# Sheet2.net
KiCad netlist of a schematic drawn in Altium Designer
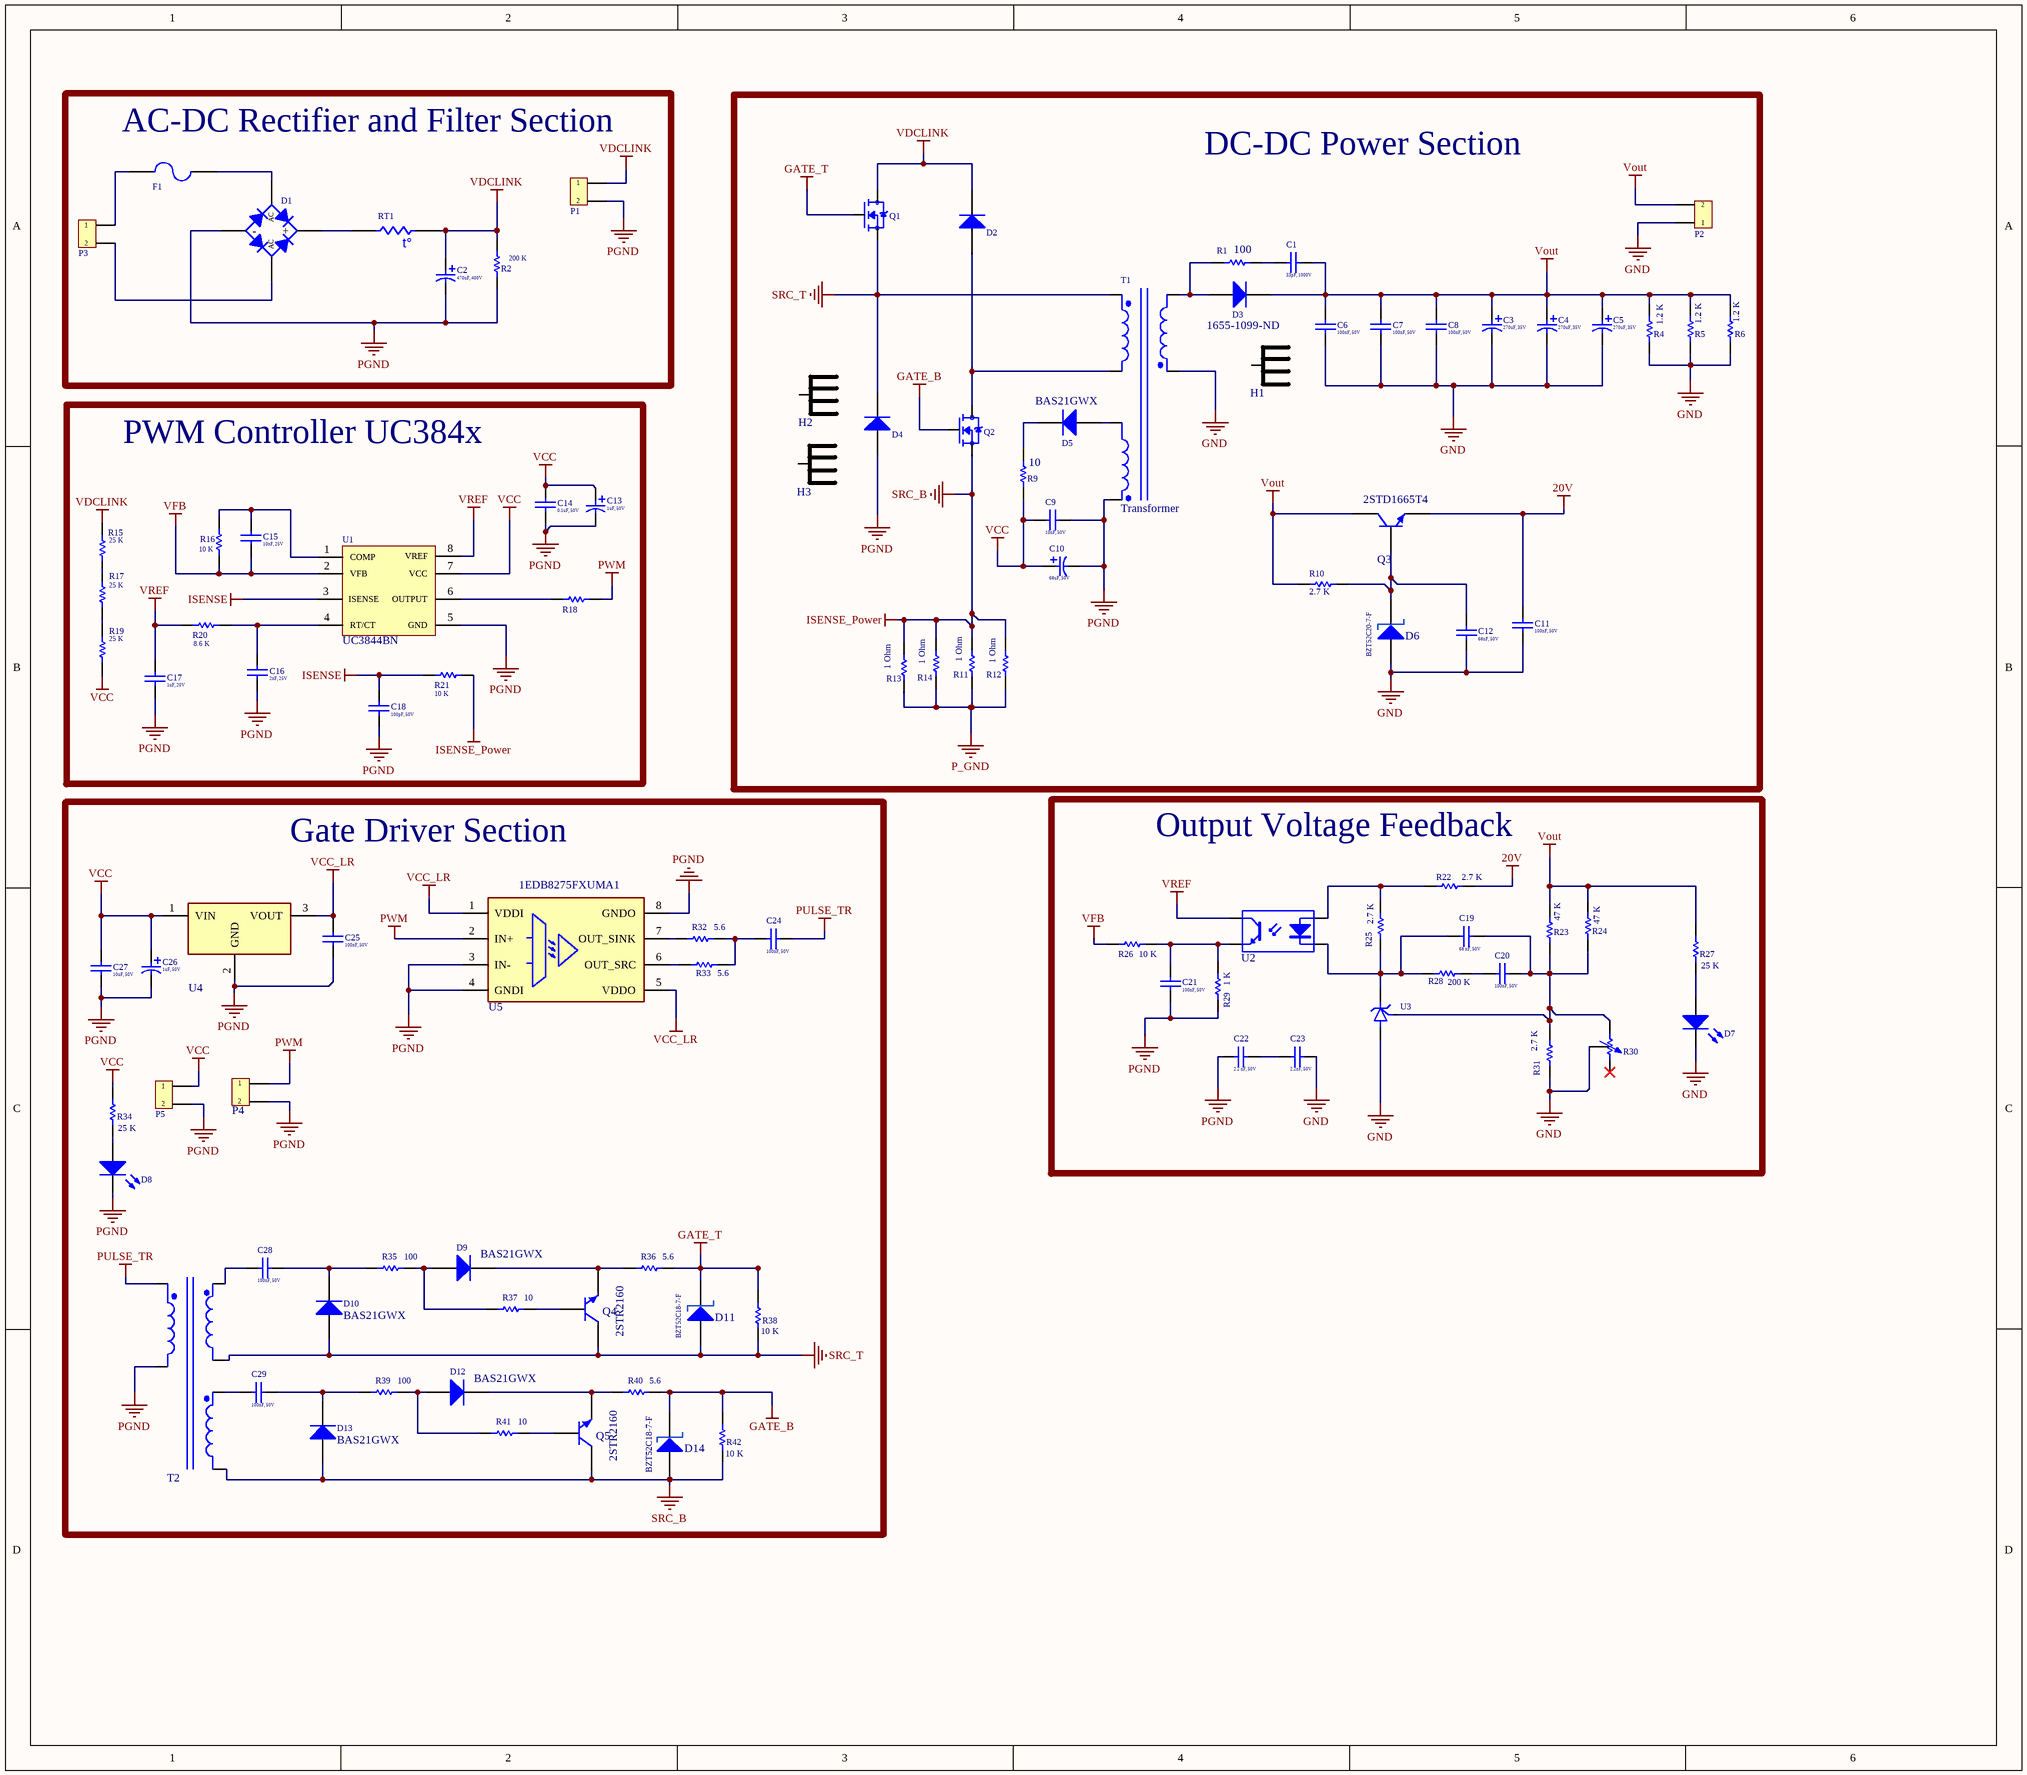
[diagram p0: Sheet2.SchDoc]

(export (version "E")
  (design (tool "Eeschema 10.0.6"))
  (components
    (comp (ref "C1")
      (value "33pF, 1000V")
      (footprint "Capacitor Polyester High Voltage DIP")
      (description "Ceramic & Polyester Capacitor")
      (fields (field (name "Comment") "(DIGIKEY Part Number)"))
      (libsource (lib "M_Derogarian Altium Library") (part "Capacitors Non-Electrolytic"))
    )
    (comp (ref "C2")
      (value "470uF, 400V")
      (footprint "Capacitor Aluminum Electrolytic DIP 20*36.5*10")
      (description "Aluminum Electrolytic Capacitors")
      (fields (field (name "MF") "Nichicon") (field (name "MP") "UVR2A471MHD"))
      (libsource (lib "M_Derogarian Altium Library") (part "Capacitors Electrolytic"))
    )
    (comp (ref "C3")
      (value "270uF, 35V")
      (footprint "Capacitor Aluminum Electrolytic DIP 10*13*5")
      (description "Aluminum Electrolytic Capacitors")
      (fields (field (name "MF") "Nichicon") (field (name "MP") "UVR2A471MHD"))
      (libsource (lib "M_Derogarian Altium Library") (part "Capacitors Electrolytic"))
    )
    (comp (ref "C4")
      (value "270uF, 35V")
      (footprint "Capacitor Aluminum Electrolytic DIP 10*13*5")
      (description "Aluminum Electrolytic Capacitors")
      (fields (field (name "MF") "Nichicon") (field (name "MP") "UVR2A471MHD"))
      (libsource (lib "M_Derogarian Altium Library") (part "Capacitors Electrolytic"))
    )
    (comp (ref "C5")
      (value "270uF, 35V")
      (footprint "Capacitor Aluminum Electrolytic DIP 10*13*5")
      (description "Aluminum Electrolytic Capacitors")
      (fields (field (name "MF") "Nichicon") (field (name "MP") "UVR2A471MHD"))
      (libsource (lib "M_Derogarian Altium Library") (part "Capacitors Electrolytic"))
    )
    (comp (ref "C6")
      (value "100nF, 50V")
      (footprint "Capacitor Ceramic SMD 1206")
      (description "Ceramic & Polyester Capacitor")
      (fields (field (name "Comment") "478-KGM21NR71H104JTTR-ND"))
      (libsource (lib "M_Derogarian Altium Library") (part "Capacitors Non-Electrolytic"))
    )
    (comp (ref "C7")
      (value "100nF, 50V")
      (footprint "Capacitor Ceramic SMD 1206")
      (description "Ceramic & Polyester Capacitor")
      (fields (field (name "Comment") "478-KGM21NR71H104JTTR-ND"))
      (libsource (lib "M_Derogarian Altium Library") (part "Capacitors Non-Electrolytic"))
    )
    (comp (ref "C8")
      (value "100nF, 50V")
      (footprint "Capacitor Ceramic SMD 1206")
      (description "Ceramic & Polyester Capacitor")
      (fields (field (name "Comment") "478-KGM21NR71H104JTTR-ND"))
      (libsource (lib "M_Derogarian Altium Library") (part "Capacitors Non-Electrolytic"))
    )
    (comp (ref "C9")
      (value "10nF, 50V")
      (footprint "Capacitor Ceramic SMD 805")
      (description "Ceramic & Polyester Capacitor")
      (fields (field (name "Comment") "GRM2195C1H103JA01D"))
      (libsource (lib "M_Derogarian Altium Library") (part "Capacitors Non-Electrolytic"))
    )
    (comp (ref "C10")
      (value "68uF, 50V")
      (footprint "Capacitor Aluminum Electrolytic DIP 5*7.5*2.5")
      (description "Aluminum Electrolytic Capacitors")
      (fields (field (name "MF") "Nichicon") (field (name "MP") "UVR2A471MHD"))
      (libsource (lib "M_Derogarian Altium Library") (part "Capacitors Electrolytic"))
    )
    (comp (ref "C11")
      (value "100nF, 50V")
      (footprint "Capacitor Ceramic SMD 1206")
      (description "Ceramic & Polyester Capacitor")
      (fields (field (name "Comment") "478-KGM21NR71H104JTTR-ND"))
      (libsource (lib "M_Derogarian Altium Library") (part "Capacitors Non-Electrolytic"))
    )
    (comp (ref "C12")
      (value "68nF, 50V")
      (footprint "Capacitor Ceramic SMD 1206")
      (description "Ceramic & Polyester Capacitor")
      (fields (field (name "Comment") "KGM21NR71H683JT"))
      (libsource (lib "M_Derogarian Altium Library") (part "Capacitors Non-Electrolytic"))
    )
    (comp (ref "C13")
      (value "1uF, 50V")
      (footprint "Capacitor Aluminum Electrolytic DIP 5*7.5*2.5")
      (description "Aluminum Electrolytic Capacitors")
      (fields (field (name "MF") "Nichicon") (field (name "MP") "UVR2A471MHD"))
      (libsource (lib "M_Derogarian Altium Library") (part "Capacitors Electrolytic"))
    )
    (comp (ref "C14")
      (value "0.1uF, 50V")
      (footprint "Capacitor Ceramic SMD 805")
      (description "Ceramic & Polyester Capacitor")
      (fields (field (name "Comment") "399-C0805C104J5RAC7800TR-ND"))
      (libsource (lib "M_Derogarian Altium Library") (part "Capacitors Non-Electrolytic"))
    )
    (comp (ref "C15")
      (value "10nF, 25V")
      (footprint "Capacitor Ceramic SMD 805")
      (description "Ceramic & Polyester Capacitor")
      (fields (field (name "Comment") "490-1642-2-ND"))
      (libsource (lib "M_Derogarian Altium Library") (part "Capacitors Non-Electrolytic"))
    )
    (comp (ref "C16")
      (value "2nF, 25V")
      (footprint "Capacitor Ceramic SMD 805")
      (description "Ceramic & Polyester Capacitor")
      (fields (field (name "Comment") "490-1627-2-ND"))
      (libsource (lib "M_Derogarian Altium Library") (part "Capacitors Non-Electrolytic"))
    )
    (comp (ref "C17")
      (value "1uF, 20V")
      (footprint "Capacitor Ceramic SMD 805")
      (description "Ceramic & Polyester Capacitor")
      (fields (field (name "Comment") "311-3498-2-ND"))
      (libsource (lib "M_Derogarian Altium Library") (part "Capacitors Non-Electrolytic"))
    )
    (comp (ref "C18")
      (value "100pF, 50V")
      (footprint "Capacitor Ceramic SMD 805")
      (description "Ceramic & Polyester Capacitor")
      (fields (field (name "Comment") "399-C0805C101J5GAC7800TR-ND"))
      (libsource (lib "M_Derogarian Altium Library") (part "Capacitors Non-Electrolytic"))
    )
    (comp (ref "C19")
      (value "68 nF, 50V")
      (footprint "Capacitor Ceramic SMD 805")
      (description "Ceramic & Polyester Capacitor")
      (fields (field (name "Comment") "KGM21NR71H683JT"))
      (libsource (lib "M_Derogarian Altium Library") (part "Capacitors Non-Electrolytic"))
    )
    (comp (ref "C20")
      (value "100nF, 50V")
      (footprint "Capacitor Ceramic SMD 805")
      (description "Ceramic & Polyester Capacitor")
      (fields (field (name "Comment") "C0805C104J5RAC7800"))
      (libsource (lib "M_Derogarian Altium Library") (part "Capacitors Non-Electrolytic"))
    )
    (comp (ref "C21")
      (value "100nF, 50V")
      (footprint "Capacitor Ceramic SMD 805")
      (description "Ceramic & Polyester Capacitor")
      (fields (field (name "Comment") "C0805C104J5RAC7800"))
      (libsource (lib "M_Derogarian Altium Library") (part "Capacitors Non-Electrolytic"))
    )
    (comp (ref "C22")
      (value "2.2 nF, 50V")
      (footprint "Capacitor Polyester High Voltage DIP")
      (description "Ceramic & Polyester Capacitor")
      (fields (field (name "Comment") "(DIGIKEY Part Number)"))
      (libsource (lib "M_Derogarian Altium Library") (part "Capacitors Non-Electrolytic"))
    )
    (comp (ref "C23")
      (value "2.2nF, 50V")
      (footprint "Capacitor Polyester High Voltage DIP")
      (description "Ceramic & Polyester Capacitor")
      (fields (field (name "Comment") "(DIGIKEY Part Number)"))
      (libsource (lib "M_Derogarian Altium Library") (part "Capacitors Non-Electrolytic"))
    )
    (comp (ref "C24")
      (value "100nF, 50V")
      (footprint "Capacitor Ceramic SMD 805")
      (description "Ceramic & Polyester Capacitor")
      (fields (field (name "Comment") "C0805C104J5RAC7800"))
      (libsource (lib "M_Derogarian Altium Library") (part "Capacitors Non-Electrolytic"))
    )
    (comp (ref "C25")
      (value "100nF, 50V")
      (footprint "Capacitor Ceramic SMD 805")
      (description "Ceramic & Polyester Capacitor")
      (fields (field (name "Comment") "C0805C104J5RAC7800"))
      (libsource (lib "M_Derogarian Altium Library") (part "Capacitors Non-Electrolytic"))
    )
    (comp (ref "C26")
      (value "1uF, 50V")
      (footprint "Capacitor Aluminum Electrolytic DIP 5*7.5*2.5")
      (description "Aluminum Electrolytic Capacitors")
      (fields (field (name "MF") "Nichicon") (field (name "MP") "UVR2A471MHD"))
      (libsource (lib "M_Derogarian Altium Library") (part "Capacitors Electrolytic"))
    )
    (comp (ref "C27")
      (value "10uF, 50V")
      (footprint "Capacitor Ceramic SMD 805")
      (description "Ceramic & Polyester Capacitor")
      (fields (field (name "Comment") "490-18663-2-ND"))
      (libsource (lib "M_Derogarian Altium Library") (part "Capacitors Non-Electrolytic"))
    )
    (comp (ref "C28")
      (value "100nF, 50V")
      (footprint "Capacitor Ceramic SMD 805")
      (description "Ceramic & Polyester Capacitor")
      (fields (field (name "Comment") "C0805C104J5RAC7800"))
      (libsource (lib "M_Derogarian Altium Library") (part "Capacitors Non-Electrolytic"))
    )
    (comp (ref "C29")
      (value "100nF, 50V")
      (footprint "Capacitor Ceramic SMD 805")
      (description "Ceramic & Polyester Capacitor")
      (fields (field (name "Comment") "C0805C104J5RAC7800"))
      (libsource (lib "M_Derogarian Altium Library") (part "Capacitors Non-Electrolytic"))
    )
    (comp (ref "D1")
      (value "31-GBU10V08-TU-ND")
      (footprint "Bridge Rectifier 1Phase 600V 10A GBJ")
      (description "Bridge Rectifier Single Phase Standard")
      (fields (field (name "PUBLISHER") "Altium Limited"))
      (libsource (lib "M_Derogarian Altium Library") (part "Single Phase Bridge Rectifier"))
    )
    (comp (ref "D2")
      (value "31-S5KP5M-13TR-ND")
      (footprint "Diode SMD POWERDI5")
      (description "Through Hole & SMD Diode")
      (fields (field (name "PUBLISHER") "Altium Limited"))
      (libsource (lib "M_Derogarian Altium Library") (part "Diode"))
    )
    (comp (ref "D3")
      (value "1655-1099-ND")
      (footprint "Diode DIP ITO-220AC")
      (description "Through Hole & SMD Diode")
      (fields (field (name "PUBLISHER") "Altium Limited"))
      (libsource (lib "M_Derogarian Altium Library") (part "Diode"))
    )
    (comp (ref "D4")
      (value "31-S5KP5M-13TR-ND")
      (footprint "Diode SMD POWERDI5")
      (description "Through Hole & SMD Diode")
      (fields (field (name "PUBLISHER") "Altium Limited"))
      (libsource (lib "M_Derogarian Altium Library") (part "Diode"))
    )
    (comp (ref "D5")
      (value "BAS21GWX")
      (footprint "Diode SMD SOD-123")
      (description "Through Hole & SMD Diode")
      (fields (field (name "PUBLISHER") "Altium Limited"))
      (libsource (lib "M_Derogarian Altium Library") (part "Diode"))
    )
    (comp (ref "D6")
      (value "BZT52C20-7-F")
      (footprint "Diode Zener SMD SOD-123 01")
      (description "Through Hole & SMD Zener Diode")
      (fields (field (name "PUBLISHER") "Altium Limited"))
      (libsource (lib "M_Derogarian Altium Library") (part "Diode Zener"))
    )
    (comp (ref "D7")
      (value "L62505TR-ND")
      (footprint "LED SMD 805 01")
      (description "Typical RED, GREEN, YELLOW, AMBER GaAs LED")
      (fields (field (name "PUBLISHER") "Altium Limited"))
      (libsource (lib "M_Derogarian Altium Library") (part "LED"))
    )
    (comp (ref "D8")
      (value "L62505TR-ND")
      (footprint "LED SMD 805 01")
      (description "Typical RED, GREEN, YELLOW, AMBER GaAs LED")
      (fields (field (name "PUBLISHER") "Altium Limited"))
      (libsource (lib "M_Derogarian Altium Library") (part "LED"))
    )
    (comp (ref "D9")
      (value "BAS21GWX")
      (footprint "Diode SMD SOD-123")
      (description "Through Hole & SMD Diode")
      (fields (field (name "PUBLISHER") "Altium Limited"))
      (libsource (lib "M_Derogarian Altium Library") (part "Diode"))
    )
    (comp (ref "D10")
      (value "BAS21GWX")
      (footprint "Diode SMD SOD-123")
      (description "Through Hole & SMD Diode")
      (fields (field (name "PUBLISHER") "Altium Limited"))
      (libsource (lib "M_Derogarian Altium Library") (part "Diode"))
    )
    (comp (ref "D11")
      (value "BZT52C18-7-F")
      (footprint "Diode Zener SMD SOD-123 01")
      (description "Through Hole & SMD Zener Diode")
      (fields (field (name "PUBLISHER") "Altium Limited"))
      (libsource (lib "M_Derogarian Altium Library") (part "Diode Zener"))
    )
    (comp (ref "D12")
      (value "BAS21GWX")
      (footprint "Diode SMD SOD-123")
      (description "Through Hole & SMD Diode")
      (fields (field (name "PUBLISHER") "Altium Limited"))
      (libsource (lib "M_Derogarian Altium Library") (part "Diode"))
    )
    (comp (ref "D13")
      (value "BAS21GWX")
      (footprint "Diode SMD SOD-123")
      (description "Through Hole & SMD Diode")
      (fields (field (name "PUBLISHER") "Altium Limited"))
      (libsource (lib "M_Derogarian Altium Library") (part "Diode"))
    )
    (comp (ref "D14")
      (value "BZT52C18-7-F")
      (footprint "Diode Zener SMD SOD-123 01")
      (description "Through Hole & SMD Zener Diode")
      (fields (field (name "PUBLISHER") "Altium Limited"))
      (libsource (lib "M_Derogarian Altium Library") (part "Diode Zener"))
    )
    (comp (ref "F1")
      (value "F1730-ND")
      (footprint "Fuse Full DIP 02")
      (description "Fuse, Circuit Protection")
      (fields (field (name "PUBLISHER") "Altium Limited"))
      (libsource (lib "M_Derogarian Altium Library") (part "Fuse"))
    )
    (comp (ref "H1")
      (value "(DIGIKEY Part Number)")
      (footprint "HEATSINK 02")
      (description "Heat Sink TO-220 Aluminum 20.0W @ 60Â°C Board Level, Vertical")
      (fields (field (name "MP") "530002B02500G") (field (name "MF") "Aavid Thermalloy"))
      (libsource (lib "M_Derogarian Altium Library") (part "Heat Sink"))
    )
    (comp (ref "H2")
      (value "(DIGIKEY Part Number)")
      (footprint "HEATSINK 02")
      (description "Heat Sink TO-220 Aluminum 20.0W @ 60Â°C Board Level, Vertical")
      (fields (field (name "MP") "530002B02500G") (field (name "MF") "Aavid Thermalloy"))
      (libsource (lib "M_Derogarian Altium Library") (part "Heat Sink"))
    )
    (comp (ref "H3")
      (value "(DIGIKEY Part Number)")
      (footprint "HEATSINK 02")
      (description "Heat Sink TO-220 Aluminum 20.0W @ 60Â°C Board Level, Vertical")
      (fields (field (name "MP") "530002B02500G") (field (name "MF") "Aavid Thermalloy"))
      (libsource (lib "M_Derogarian Altium Library") (part "Heat Sink"))
    )
    (comp (ref "P1")
      (value "732-2088-ND")
      (footprint "Phoenix Contact 2x Male Straight")
      (description "Contact-Phoenix 2x")
      (fields
        (field (name "MANUFACTURER") "Phoenix Contact")
        (field (name "MANUFACTURER PART NUMBER") "1715721")
      )
      (libsource (lib "M_Derogarian Altium Library") (part "Contact-Phoenix 2x"))
    )
    (comp (ref "P2")
      (value "732-2088-ND")
      (footprint "Phoenix Contact 2x Male Straight")
      (description "Contact-Phoenix 2x")
      (fields
        (field (name "MANUFACTURER") "Phoenix Contact")
        (field (name "MANUFACTURER PART NUMBER") "1715721")
      )
      (libsource (lib "") (part "Contact-Phoenix 2x_1"))
    )
    (comp (ref "P3")
      (value "732-2088-ND")
      (footprint "Phoenix Contact 2x Male Straight")
      (description "Contact-Phoenix 2x")
      (fields
        (field (name "MANUFACTURER") "Phoenix Contact")
        (field (name "MANUFACTURER PART NUMBER") "1715721")
      )
      (libsource (lib "M_Derogarian Altium Library") (part "Contact-Phoenix 2x"))
    )
    (comp (ref "P4")
      (value "A105225-ND")
      (footprint "Header 01 1x2")
      (description "Contact-Phoenix 2x")
      (fields
        (field (name "MANUFACTURER") "Phoenix Contact")
        (field (name "MANUFACTURER PART NUMBER") "1715721")
      )
      (libsource (lib "M_Derogarian Altium Library") (part "Contact-Phoenix 2x"))
    )
    (comp (ref "P5")
      (value "732-2088-ND")
      (footprint "Phoenix Contact 2x Male Straight")
      (description "Contact-Phoenix 2x")
      (fields
        (field (name "MANUFACTURER") "Phoenix Contact")
        (field (name "MANUFACTURER PART NUMBER") "1715721")
      )
      (libsource (lib "M_Derogarian Altium Library") (part "Contact-Phoenix 2x"))
    )
    (comp (ref "Q1")
      (value "IPP50R280CEXKSA1-ND")
      (footprint "MOSFET DIP TO-220")
      (description "N-Channel MOSFET")
      (fields (field (name "MP") "FDN360P") (field (name "MF") "ON Semiconductor"))
      (libsource (lib "M_Derogarian Altium Library") (part "Transistor MOSFET"))
    )
    (comp (ref "Q2")
      (value "IPP50R280CEXKSA1-ND")
      (footprint "MOSFET DIP TO-220")
      (description "N-Channel MOSFET")
      (fields (field (name "MP") "FDN360P") (field (name "MF") "ON Semiconductor"))
      (libsource (lib "M_Derogarian Altium Library") (part "Transistor MOSFET"))
    )
    (comp (ref "Q3")
      (value "2STD1665T4")
      (footprint "BJT NPN SMD DPAK TO-252")
      (description "NPN General Purpose BJT")
      (fields (field (name "PUBLISHER") "Altium Limited"))
      (libsource (lib "M_Derogarian Altium Library") (part "Transistor BJT"))
    )
    (comp (ref "Q4")
      (value "2STR2160")
      (footprint "BJT NPN SMD SOT-23")
      (description "NPN General Purpose BJT")
      (fields (field (name "PUBLISHER") "Altium Limited"))
      (libsource (lib "M_Derogarian Altium Library") (part "Transistor BJT"))
    )
    (comp (ref "Q5")
      (value "2STR2160")
      (footprint "BJT NPN SMD SOT-23")
      (description "NPN General Purpose BJT")
      (fields (field (name "PUBLISHER") "Altium Limited"))
      (libsource (lib "M_Derogarian Altium Library") (part "Transistor BJT"))
    )
    (comp (ref "R1")
      (value "100")
      (footprint "Resistor DIP 0.25W 01")
      (description "Through Hole & SMD")
      (fields (field (name "Comment") "(DIGIKEY Part Number)") (field (name "PUBLISHER") "Altium Limited"))
      (libsource (lib "M_Derogarian Altium Library") (part "Resistor"))
    )
    (comp (ref "R2")
      (value "200 K")
      (footprint "Resistor DIP 0.25W 01")
      (description "Through Hole & SMD")
      (fields (field (name "Comment") "P200KDATR-ND") (field (name "PUBLISHER") "Altium Limited"))
      (libsource (lib "M_Derogarian Altium Library") (part "Resistor"))
    )
    (comp (ref "R4")
      (value "1.2 K")
      (footprint "Resistor SMD 1206")
      (description "Through Hole & SMD")
      (fields (field (name "Comment") "RMCF2010JT1K20") (field (name "PUBLISHER") "Altium Limited"))
      (libsource (lib "M_Derogarian Altium Library") (part "Resistor"))
    )
    (comp (ref "R5")
      (value "1.2 K")
      (footprint "Resistor SMD 1206")
      (description "Through Hole & SMD")
      (fields (field (name "Comment") "RMCF2010JT1K20") (field (name "PUBLISHER") "Altium Limited"))
      (libsource (lib "M_Derogarian Altium Library") (part "Resistor"))
    )
    (comp (ref "R6")
      (value "1.2 K")
      (footprint "Resistor SMD 1206")
      (description "Through Hole & SMD")
      (fields (field (name "Comment") "RMCF2010JT1K20") (field (name "PUBLISHER") "Altium Limited"))
      (libsource (lib "M_Derogarian Altium Library") (part "Resistor"))
    )
    (comp (ref "R9")
      (value "10")
      (footprint "Resistor SMD 805")
      (description "Through Hole & SMD")
      (fields (field (name "Comment") "(DIGIKEY Part Number)") (field (name "PUBLISHER") "Altium Limited"))
      (libsource (lib "M_Derogarian Altium Library") (part "Resistor"))
    )
    (comp (ref "R10")
      (value "2.7 K")
      (footprint "Resistor SMD 805")
      (description "Through Hole & SMD")
      (fields (field (name "Comment") "P2.7KDATR-ND") (field (name "PUBLISHER") "Altium Limited"))
      (libsource (lib "M_Derogarian Altium Library") (part "Resistor"))
    )
    (comp (ref "R11")
      (value "1 Ohm")
      (footprint "Resistor SMD 1206")
      (description "Through Hole & SMD")
      (fields (field (name "Comment") "13-RT1206BRE071RL-ND") (field (name "PUBLISHER") "Altium Limited"))
      (libsource (lib "M_Derogarian Altium Library") (part "Resistor"))
    )
    (comp (ref "R12")
      (value "1 Ohm")
      (footprint "Resistor SMD 1206")
      (description "Through Hole & SMD")
      (fields (field (name "Comment") "13-RT1206BRE071RL-ND") (field (name "PUBLISHER") "Altium Limited"))
      (libsource (lib "M_Derogarian Altium Library") (part "Resistor"))
    )
    (comp (ref "R13")
      (value "1 Ohm")
      (footprint "Resistor SMD 1206")
      (description "Through Hole & SMD")
      (fields (field (name "Comment") "13-RT1206BRE071RL-ND") (field (name "PUBLISHER") "Altium Limited"))
      (libsource (lib "M_Derogarian Altium Library") (part "Resistor"))
    )
    (comp (ref "R14")
      (value "1 Ohm")
      (footprint "Resistor SMD 1206")
      (description "Through Hole & SMD")
      (fields (field (name "Comment") "13-RT1206BRE071RL-ND") (field (name "PUBLISHER") "Altium Limited"))
      (libsource (lib "M_Derogarian Altium Library") (part "Resistor"))
    )
    (comp (ref "R15")
      (value "25 K")
      (footprint "Resistor SMD 805")
      (description "Through Hole & SMD")
      (fields (field (name "Comment") "A121556TR-ND") (field (name "PUBLISHER") "Altium Limited"))
      (libsource (lib "M_Derogarian Altium Library") (part "Resistor"))
    )
    (comp (ref "R16")
      (value "10 K")
      (footprint "Resistor SMD 805")
      (description "Through Hole & SMD")
      (fields (field (name "Comment") "RG20P10.0KBTR-ND") (field (name "PUBLISHER") "Altium Limited"))
      (libsource (lib "M_Derogarian Altium Library") (part "Resistor"))
    )
    (comp (ref "R17")
      (value "25 K")
      (footprint "Resistor SMD 805")
      (description "Through Hole & SMD")
      (fields (field (name "Comment") "A121556TR-ND") (field (name "PUBLISHER") "Altium Limited"))
      (libsource (lib "M_Derogarian Altium Library") (part "Resistor"))
    )
    (comp (ref "R18")
      (value "MCU0805MZ0000ZP500")
      (footprint "Resistor SMD 805")
      (description "Through Hole & SMD")
      (fields (field (name "PUBLISHER") "Altium Limited"))
      (libsource (lib "M_Derogarian Altium Library") (part "Resistor"))
    )
    (comp (ref "R19")
      (value "25 K")
      (footprint "Resistor SMD 805")
      (description "Through Hole & SMD")
      (fields (field (name "Comment") "A121556TR-ND") (field (name "PUBLISHER") "Altium Limited"))
      (libsource (lib "M_Derogarian Altium Library") (part "Resistor"))
    )
    (comp (ref "R20")
      (value "8.6 K")
      (footprint "Resistor SMD 805")
      (description "Through Hole & SMD")
      (fields (field (name "Comment") "P8.66KDATR-ND") (field (name "PUBLISHER") "Altium Limited"))
      (libsource (lib "M_Derogarian Altium Library") (part "Resistor"))
    )
    (comp (ref "R21")
      (value "10 K")
      (footprint "Resistor SMD 805")
      (description "Through Hole & SMD")
      (fields (field (name "Comment") "RG20P10.0KBTR-ND") (field (name "PUBLISHER") "Altium Limited"))
      (libsource (lib "M_Derogarian Altium Library") (part "Resistor"))
    )
    (comp (ref "R22")
      (value "2.7 K")
      (footprint "Resistor SMD 805")
      (description "Through Hole & SMD")
      (fields (field (name "Comment") "P2.7KDATR-ND") (field (name "PUBLISHER") "Altium Limited"))
      (libsource (lib "M_Derogarian Altium Library") (part "Resistor"))
    )
    (comp (ref "R23")
      (value "47 K")
      (footprint "Resistor SMD 805")
      (description "Through Hole & SMD")
      (fields (field (name "Comment") "ERA-6AEB473V") (field (name "PUBLISHER") "Altium Limited"))
      (libsource (lib "M_Derogarian Altium Library") (part "Resistor"))
    )
    (comp (ref "R24")
      (value "47 K")
      (footprint "Resistor SMD 805")
      (description "Through Hole & SMD")
      (fields (field (name "Comment") "ERA-6AEB473V") (field (name "PUBLISHER") "Altium Limited"))
      (libsource (lib "M_Derogarian Altium Library") (part "Resistor"))
    )
    (comp (ref "R25")
      (value "2.7 K")
      (footprint "Resistor SMD 805")
      (description "Through Hole & SMD")
      (fields (field (name "Comment") "P2.7KDATR-ND") (field (name "PUBLISHER") "Altium Limited"))
      (libsource (lib "M_Derogarian Altium Library") (part "Resistor"))
    )
    (comp (ref "R26")
      (value "10 K")
      (footprint "Resistor SMD 805")
      (description "Through Hole & SMD")
      (fields (field (name "Comment") "RG20P10.0KBTR-ND") (field (name "PUBLISHER") "Altium Limited"))
      (libsource (lib "M_Derogarian Altium Library") (part "Resistor"))
    )
    (comp (ref "R27")
      (value "25 K")
      (footprint "Resistor SMD 805")
      (description "Through Hole & SMD")
      (fields (field (name "Comment") "CPF0805B25KE1") (field (name "PUBLISHER") "Altium Limited"))
      (libsource (lib "M_Derogarian Altium Library") (part "Resistor"))
    )
    (comp (ref "R28")
      (value "200 K")
      (footprint "Resistor SMD 805")
      (description "Through Hole & SMD")
      (fields (field (name "Comment") "P200KDATR-ND") (field (name "PUBLISHER") "Altium Limited"))
      (libsource (lib "M_Derogarian Altium Library") (part "Resistor"))
    )
    (comp (ref "R29")
      (value "1 K")
      (footprint "Resistor SMD 805")
      (description "Through Hole & SMD")
      (fields (field (name "Comment") "ERA-6AEB102V") (field (name "PUBLISHER") "Altium Limited"))
      (libsource (lib "M_Derogarian Altium Library") (part "Resistor"))
    )
    (comp (ref "R30")
      (value "(DIGIKEY Part Number)")
      (footprint "Resistor Variable DIP 02")
      (description "Trimmer Potentiometer Cermet Top Adjustment")
      (fields (field (name "PUBLISHER") "Altium Limited"))
      (libsource (lib "M_Derogarian Altium Library") (part "Resistor Variable"))
    )
    (comp (ref "R31")
      (value "2.7 K")
      (footprint "Resistor SMD 805")
      (description "Through Hole & SMD")
      (fields (field (name "Comment") "ERA-6AEB272V") (field (name "PUBLISHER") "Altium Limited"))
      (libsource (lib "M_Derogarian Altium Library") (part "Resistor"))
    )
    (comp (ref "R32")
      (value "5.6")
      (footprint "Resistor SMD 1206 MELF 01")
      (description "Through Hole & SMD")
      (fields (field (name "Comment") "749-1374-2-ND") (field (name "PUBLISHER") "Altium Limited"))
      (libsource (lib "M_Derogarian Altium Library") (part "Resistor"))
    )
    (comp (ref "R33")
      (value "5.6")
      (footprint "Resistor SMD 1206 MELF 01")
      (description "Through Hole & SMD")
      (fields (field (name "Comment") "749-1374-2-ND") (field (name "PUBLISHER") "Altium Limited"))
      (libsource (lib "M_Derogarian Altium Library") (part "Resistor"))
    )
    (comp (ref "R34")
      (value "25 K")
      (footprint "Resistor SMD 805")
      (description "Through Hole & SMD")
      (fields (field (name "Comment") "CPF0805B25KE1") (field (name "PUBLISHER") "Altium Limited"))
      (libsource (lib "M_Derogarian Altium Library") (part "Resistor"))
    )
    (comp (ref "R35")
      (value "100")
      (footprint "Resistor SMD 805")
      (description "Through Hole & SMD")
      (fields (field (name "Comment") "13-AC0805FR-7W100RLTR-ND") (field (name "PUBLISHER") "Altium Limited"))
      (libsource (lib "M_Derogarian Altium Library") (part "Resistor"))
    )
    (comp (ref "R36")
      (value "5.6")
      (footprint "Resistor SMD 1206 MELF 01")
      (description "Through Hole & SMD")
      (fields (field (name "Comment") "749-1374-2-ND") (field (name "PUBLISHER") "Altium Limited"))
      (libsource (lib "M_Derogarian Altium Library") (part "Resistor"))
    )
    (comp (ref "R37")
      (value "10")
      (footprint "Resistor SMD 805")
      (description "Through Hole & SMD")
      (fields (field (name "Comment") "CRS0805-FX-10R0ELFTR-ND") (field (name "PUBLISHER") "Altium Limited"))
      (libsource (lib "M_Derogarian Altium Library") (part "Resistor"))
    )
    (comp (ref "R38")
      (value "10 K")
      (footprint "Resistor SMD 805")
      (description "Through Hole & SMD")
      (fields (field (name "Comment") "RG2012P-103-B-T5") (field (name "PUBLISHER") "Altium Limited"))
      (libsource (lib "M_Derogarian Altium Library") (part "Resistor"))
    )
    (comp (ref "R39")
      (value "100")
      (footprint "Resistor SMD 805")
      (description "Through Hole & SMD")
      (fields (field (name "Comment") "13-AC0805FR-7W100RLTR-ND") (field (name "PUBLISHER") "Altium Limited"))
      (libsource (lib "M_Derogarian Altium Library") (part "Resistor"))
    )
    (comp (ref "R40")
      (value "5.6")
      (footprint "Resistor SMD 1206 MELF 01")
      (description "Through Hole & SMD")
      (fields (field (name "Comment") "749-1374-2-ND") (field (name "PUBLISHER") "Altium Limited"))
      (libsource (lib "M_Derogarian Altium Library") (part "Resistor"))
    )
    (comp (ref "R41")
      (value "10")
      (footprint "Resistor SMD 805")
      (description "Through Hole & SMD")
      (fields (field (name "Comment") "CRS0805-FX-10R0ELFTR-ND") (field (name "PUBLISHER") "Altium Limited"))
      (libsource (lib "M_Derogarian Altium Library") (part "Resistor"))
    )
    (comp (ref "R42")
      (value "10 K")
      (footprint "Resistor SMD 805")
      (description "Through Hole & SMD")
      (fields (field (name "Comment") "RG2012P-103-B-T5") (field (name "PUBLISHER") "Altium Limited"))
      (libsource (lib "M_Derogarian Altium Library") (part "Resistor"))
    )
    (comp (ref "RT1")
      (value "118-BN-LG10Y2R0MYB-ND")
      (footprint "NTC Thermistor DIP 01")
      (description "NTC Thermistor")
      (fields (field (name "PUBLISHER") "Altium Limited"))
      (libsource (lib "M_Derogarian Altium Library") (part "NTC"))
    )
    (comp (ref "T1")
      (value "Transformer")
      (footprint "Transformer EE42/21/20")
      (description "Transformer (Ideal)")
      (fields (field (name "PUBLISHER") "Altium Limited"))
      (libsource (lib "M_Derogarian Altium Library") (part "Transformer EE42/21/20"))
    )
    (comp (ref "T2")
      (value "Transformer 8 Output")
      (footprint "Pulse Transformer 02")
      (description "Driver Transformer")
      (fields (field (name "PUBLISHER") "Altium Limited"))
      (libsource (lib "M_Derogarian Altium Library") (part "Pulse Transformer 1{colon}1{colon}1"))
    )
    (comp (ref "U1")
      (value "UC3844BN")
      (footprint "PWM Controller UC3844 DIP 01")
      (description "Off-Line Controllers 52kHz 1A Current PWM No-Cancel/No-Return")
      (fields (field (name "MANUFACTURER") "STMicroelectronics"))
      (libsource (lib "M_Derogarian Altium Library") (part "PWM Controller UC3844BN"))
    )
    (comp (ref "U2")
      (value "PS2501-1-H-A")
      (footprint "Optoisolators DIP 01")
      (description "Optoisolator Transistor Output 5000Vrms 1 Channel 4-DIP")
      (fields (field (name "PUBLISHER") "Altium Limited"))
      (libsource (lib "M_Derogarian Altium Library") (part "Optoisolator"))
    )
    (comp (ref "U3")
      (value "(DIGIKEY Part Number)")
      (footprint "TL431 SMD 02")
      (description "Shunt Voltage Reference IC")
      (fields (field (name "MP") "TL431ILP") (field (name "MF") "Microsemi Corporation"))
      (libsource (lib "M_Derogarian Altium Library") (part "TL431"))
    )
    (comp (ref "U4")
      (value "LM2940SX-12/NOPBTR-ND")
      (footprint "Linear Regulator DIP TO-263")
      (description "Voltage Regulators - Linear, Low Drop Out (LDO) Regulators")
      (fields
        (field (name "MANUFACTURER") "STMicroelectronics")
        (field (name "MANUFACTURER PART NUMBER") "LD1117DT33")
      )
      (libsource (lib "M_Derogarian Altium Library") (part "Linear Regulator"))
    )
    (comp (ref "U5")
      (value "1EDB8275FXUMA1")
      (footprint "Gate Driver 1EDB8275FXUMA1 SMD 01")
      (description "Gate Driver Ic, 1-Ch, 3V-15V, 9.8A, Dso Rohs Compliant: Yes ¦Infineon 1EDB8275FXUMA1")
      (fields (field (name "MANUFACTURER") "Infineon"))
      (libsource (lib "M_Derogarian Altium Library") (part "Gate Driver Infineon"))
    )
  )
  (nets
    (net (code "1") (name "20V") (class "Default")
      (node (ref "C11") (pin "2") (pinfunction "2_2") (pintype "passive"))
      (node (ref "Q3") (pin "2") (pinfunction "E_2") (pintype "passive"))
      (node (ref "R22") (pin "1") (pinfunction "1_1") (pintype "passive"))
    )
    (net (code "2") (name "GATE_B") (class "Default")
      (node (ref "D14") (pin "2") (pinfunction "K_2") (pintype "passive"))
      (node (ref "Q2") (pin "1") (pinfunction "G_1") (pintype "passive"))
      (node (ref "R40") (pin "1") (pinfunction "1_1") (pintype "passive"))
      (node (ref "R42") (pin "1") (pinfunction "1_1") (pintype "passive"))
    )
    (net (code "3") (name "GATE_T") (class "Default")
      (node (ref "D11") (pin "2") (pinfunction "K_2") (pintype "passive"))
      (node (ref "Q1") (pin "1") (pinfunction "G_1") (pintype "passive"))
      (node (ref "R36") (pin "1") (pinfunction "1_1") (pintype "passive"))
      (node (ref "R38") (pin "1") (pinfunction "1_1") (pintype "passive"))
    )
    (net (code "4") (name "GND") (class "Default")
      (node (ref "C11") (pin "1") (pinfunction "1_1") (pintype "passive"))
      (node (ref "C12") (pin "1") (pinfunction "1_1") (pintype "passive"))
      (node (ref "C23") (pin "2") (pinfunction "2_2") (pintype "passive"))
      (node (ref "C3") (pin "2") (pinfunction "2_2") (pintype "passive"))
      (node (ref "C4") (pin "2") (pinfunction "2_2") (pintype "passive"))
      (node (ref "C5") (pin "2") (pinfunction "2_2") (pintype "passive"))
      (node (ref "C6") (pin "1") (pinfunction "1_1") (pintype "passive"))
      (node (ref "C7") (pin "1") (pinfunction "1_1") (pintype "passive"))
      (node (ref "C8") (pin "1") (pinfunction "1_1") (pintype "passive"))
      (node (ref "D6") (pin "1") (pinfunction "A_1") (pintype "passive"))
      (node (ref "D7") (pin "2") (pinfunction "K_2") (pintype "passive"))
      (node (ref "P2") (pin "1") (pinfunction "1_1") (pintype "power_in"))
      (node (ref "R30") (pin "2") (pinfunction "2_2") (pintype "passive"))
      (node (ref "R31") (pin "2") (pinfunction "2_2") (pintype "passive"))
      (node (ref "R4") (pin "2") (pinfunction "2_2") (pintype "passive"))
      (node (ref "R5") (pin "2") (pinfunction "2_2") (pintype "passive"))
      (node (ref "R6") (pin "2") (pinfunction "2_2") (pintype "passive"))
      (node (ref "T1") (pin "6") (pinfunction "6_6") (pintype "passive"))
      (node (ref "U3") (pin "2") (pinfunction "A_2") (pintype "passive"))
    )
    (net (code "5") (name "ISENSE") (class "Default")
      (node (ref "C18") (pin "2") (pinfunction "2_2") (pintype "passive"))
      (node (ref "R21") (pin "2") (pinfunction "2_2") (pintype "passive"))
      (node (ref "U1") (pin "3") (pinfunction "ISENSE_3") (pintype "passive"))
    )
    (net (code "6") (name "ISENSE_Power") (class "Default")
      (node (ref "D13") (pin "1") (pinfunction "A_1") (pintype "passive"))
      (node (ref "D14") (pin "1") (pinfunction "A_1") (pintype "passive"))
      (node (ref "Q2") (pin "3") (pinfunction "S_3") (pintype "passive"))
      (node (ref "Q5") (pin "3") (pinfunction "C_3") (pintype "passive"))
      (node (ref "R11") (pin "2") (pinfunction "2_2") (pintype "passive"))
      (node (ref "R12") (pin "2") (pinfunction "2_2") (pintype "passive"))
      (node (ref "R13") (pin "2") (pinfunction "2_2") (pintype "passive"))
      (node (ref "R14") (pin "2") (pinfunction "2_2") (pintype "passive"))
      (node (ref "R21") (pin "1") (pinfunction "1_1") (pintype "passive"))
      (node (ref "R42") (pin "2") (pinfunction "2_2") (pintype "passive"))
      (node (ref "T2") (pin "5") (pinfunction "5_5") (pintype "passive"))
    )
    (net (code "7") (name "Net-(C1-Pad2)") (class "Default")
      (node (ref "C1") (pin "2") (pinfunction "2_2") (pintype "passive"))
      (node (ref "R1") (pin "1") (pinfunction "1_1") (pintype "passive"))
    )
    (net (code "8") (name "Net-(C20-Pad2)") (class "Default")
      (node (ref "C20") (pin "2") (pinfunction "2_2") (pintype "passive"))
      (node (ref "R28") (pin "2") (pinfunction "2_2") (pintype "passive"))
    )
    (net (code "9") (name "Net-(C22-Pad2)") (class "Default")
      (node (ref "C22") (pin "2") (pinfunction "2_2") (pintype "passive"))
      (node (ref "C23") (pin "1") (pinfunction "1_1") (pintype "passive"))
    )
    (net (code "10") (name "Net-(C24-Pad2)") (class "Default")
      (node (ref "C24") (pin "2") (pinfunction "2_2") (pintype "passive"))
      (node (ref "R32") (pin "1") (pinfunction "1_1") (pintype "passive"))
      (node (ref "R33") (pin "1") (pinfunction "1_1") (pintype "passive"))
    )
    (net (code "11") (name "Net-(C28-Pad2)") (class "Default")
      (node (ref "C28") (pin "2") (pinfunction "2_2") (pintype "passive"))
      (node (ref "T2") (pin "3") (pinfunction "3_3") (pintype "passive"))
    )
    (net (code "12") (name "Net-(C29-Pad2)") (class "Default")
      (node (ref "C29") (pin "2") (pinfunction "2_2") (pintype "passive"))
      (node (ref "T2") (pin "6") (pinfunction "6_6") (pintype "passive"))
    )
    (net (code "13") (name "Net-(D1-+)") (class "Default")
      (node (ref "D1") (pin "4") (pinfunction "+_4") (pintype "passive"))
      (node (ref "RT1") (pin "1") (pinfunction "1_1") (pintype "passive"))
    )
    (net (code "14") (name "Net-(D1-AC-Pad1)") (class "Default")
      (node (ref "D1") (pin "1") (pinfunction "AC_1") (pintype "passive"))
      (node (ref "F1") (pin "2") (pinfunction "2_2") (pintype "passive"))
    )
    (net (code "15") (name "Net-(D1-AC-Pad2)") (class "Default")
      (node (ref "D1") (pin "2") (pinfunction "AC_2") (pintype "passive"))
      (node (ref "P3") (pin "2") (pinfunction "2_2") (pintype "power_in"))
    )
    (net (code "16") (name "Net-(D2-A)") (class "Default")
      (node (ref "D2") (pin "1") (pinfunction "A_1") (pintype "passive"))
      (node (ref "Q2") (pin "2") (pinfunction "D_2") (pintype "passive"))
      (node (ref "T1") (pin "2") (pinfunction "2_2") (pintype "passive"))
    )
    (net (code "17") (name "Net-(D3-A)") (class "Default")
      (node (ref "D3") (pin "1") (pinfunction "A_1") (pintype "passive"))
      (node (ref "R1") (pin "2") (pinfunction "2_2") (pintype "passive"))
      (node (ref "T1") (pin "5") (pinfunction "3_5") (pintype "passive"))
    )
    (net (code "18") (name "Net-(D5-A)") (class "Default")
      (node (ref "D5") (pin "1") (pinfunction "A_1") (pintype "passive"))
      (node (ref "T1") (pin "3") (pinfunction "3_3") (pintype "passive"))
    )
    (net (code "19") (name "Net-(D5-K)") (class "Default")
      (node (ref "D5") (pin "2") (pinfunction "K_2") (pintype "passive"))
      (node (ref "R9") (pin "1") (pinfunction "1_1") (pintype "passive"))
    )
    (net (code "20") (name "Net-(D6-K)") (class "Default")
      (node (ref "C12") (pin "2") (pinfunction "2_2") (pintype "passive"))
      (node (ref "D6") (pin "2") (pinfunction "K_2") (pintype "passive"))
      (node (ref "Q3") (pin "1") (pinfunction "B_1") (pintype "passive"))
      (node (ref "R10") (pin "2") (pinfunction "2_2") (pintype "passive"))
    )
    (net (code "21") (name "Net-(D7-A)") (class "Default")
      (node (ref "D7") (pin "1") (pinfunction "A_1") (pintype "passive"))
      (node (ref "R27") (pin "2") (pinfunction "2_2") (pintype "passive"))
    )
    (net (code "22") (name "Net-(D8-A)") (class "Default")
      (node (ref "D8") (pin "1") (pinfunction "A_1") (pintype "passive"))
      (node (ref "R34") (pin "2") (pinfunction "2_2") (pintype "passive"))
    )
    (net (code "23") (name "Net-(D9-A)") (class "Default")
      (node (ref "D9") (pin "1") (pinfunction "A_1") (pintype "passive"))
      (node (ref "R35") (pin "1") (pinfunction "1_1") (pintype "passive"))
      (node (ref "R37") (pin "2") (pinfunction "2_2") (pintype "passive"))
    )
    (net (code "24") (name "Net-(D9-K)") (class "Default")
      (node (ref "D9") (pin "2") (pinfunction "K_2") (pintype "passive"))
      (node (ref "Q4") (pin "2") (pinfunction "E_2") (pintype "passive"))
      (node (ref "R36") (pin "2") (pinfunction "2_2") (pintype "passive"))
    )
    (net (code "25") (name "Net-(D10-K)") (class "Default")
      (node (ref "C28") (pin "1") (pinfunction "1_1") (pintype "passive"))
      (node (ref "D10") (pin "2") (pinfunction "K_2") (pintype "passive"))
      (node (ref "R35") (pin "2") (pinfunction "2_2") (pintype "passive"))
    )
    (net (code "26") (name "Net-(D12-A)") (class "Default")
      (node (ref "D12") (pin "1") (pinfunction "A_1") (pintype "passive"))
      (node (ref "R39") (pin "1") (pinfunction "1_1") (pintype "passive"))
      (node (ref "R41") (pin "2") (pinfunction "2_2") (pintype "passive"))
    )
    (net (code "27") (name "Net-(D12-K)") (class "Default")
      (node (ref "D12") (pin "2") (pinfunction "K_2") (pintype "passive"))
      (node (ref "Q5") (pin "2") (pinfunction "E_2") (pintype "passive"))
      (node (ref "R40") (pin "2") (pinfunction "2_2") (pintype "passive"))
    )
    (net (code "28") (name "Net-(D13-K)") (class "Default")
      (node (ref "C29") (pin "1") (pinfunction "1_1") (pintype "passive"))
      (node (ref "D13") (pin "2") (pinfunction "K_2") (pintype "passive"))
      (node (ref "R39") (pin "2") (pinfunction "2_2") (pintype "passive"))
    )
    (net (code "29") (name "Net-(F1-Pad1)") (class "Default")
      (node (ref "F1") (pin "1") (pinfunction "1_1") (pintype "passive"))
      (node (ref "P3") (pin "1") (pinfunction "1_1") (pintype "power_in"))
    )
    (net (code "30") (name "Net-(Q4-B)") (class "Default")
      (node (ref "Q4") (pin "1") (pinfunction "B_1") (pintype "passive"))
      (node (ref "R37") (pin "1") (pinfunction "1_1") (pintype "passive"))
    )
    (net (code "31") (name "Net-(Q5-B)") (class "Default")
      (node (ref "Q5") (pin "1") (pinfunction "B_1") (pintype "passive"))
      (node (ref "R41") (pin "1") (pinfunction "1_1") (pintype "passive"))
    )
    (net (code "32") (name "Net-(R15-Pad2)") (class "Default")
      (node (ref "R15") (pin "2") (pinfunction "2_2") (pintype "passive"))
      (node (ref "R17") (pin "1") (pinfunction "1_1") (pintype "passive"))
    )
    (net (code "33") (name "Net-(R17-Pad2)") (class "Default")
      (node (ref "R17") (pin "2") (pinfunction "2_2") (pintype "passive"))
      (node (ref "R19") (pin "1") (pinfunction "1_1") (pintype "passive"))
    )
    (net (code "34") (name "Net-(U1-COMP)") (class "Default")
      (node (ref "C15") (pin "2") (pinfunction "2_2") (pintype "passive"))
      (node (ref "R16") (pin "2") (pinfunction "2_2") (pintype "passive"))
      (node (ref "U1") (pin "1") (pinfunction "COMP_1") (pintype "passive"))
    )
    (net (code "35") (name "Net-(U1-OUTPUT)") (class "Default")
      (node (ref "R18") (pin "1") (pinfunction "1_1") (pintype "passive"))
      (node (ref "U1") (pin "6") (pinfunction "OUTPUT_6") (pintype "passive"))
    )
    (net (code "36") (name "Net-(U1-RT{slash}CT)") (class "Default")
      (node (ref "C16") (pin "2") (pinfunction "2_2") (pintype "passive"))
      (node (ref "R20") (pin "1") (pinfunction "1_1") (pintype "passive"))
      (node (ref "U1") (pin "4") (pinfunction "RT/CT_4") (pintype "passive"))
    )
    (net (code "37") (name "Net-(U2-A)") (class "Default")
      (node (ref "R22") (pin "2") (pinfunction "2_2") (pintype "passive"))
      (node (ref "R25") (pin "1") (pinfunction "1_1") (pintype "passive"))
      (node (ref "U2") (pin "1") (pinfunction "A_1") (pintype "passive"))
    )
    (net (code "38") (name "Net-(U2-E)") (class "Default")
      (node (ref "C21") (pin "1") (pinfunction "1_1") (pintype "passive"))
      (node (ref "R26") (pin "2") (pinfunction "2_2") (pintype "passive"))
      (node (ref "R29") (pin "1") (pinfunction "1_1") (pintype "passive"))
      (node (ref "U2") (pin "3") (pinfunction "E_3") (pintype "passive"))
    )
    (net (code "39") (name "Net-(U2-K)") (class "Default")
      (node (ref "C19") (pin "2") (pinfunction "2_2") (pintype "passive"))
      (node (ref "R25") (pin "2") (pinfunction "2_2") (pintype "passive"))
      (node (ref "R28") (pin "1") (pinfunction "1_1") (pintype "passive"))
      (node (ref "U2") (pin "2") (pinfunction "K_2") (pintype "passive"))
      (node (ref "U3") (pin "3") (pinfunction "C_3") (pintype "passive"))
    )
    (net (code "40") (name "Net-(U3-REF)") (class "Default")
      (node (ref "C19") (pin "1") (pinfunction "1_1") (pintype "passive"))
      (node (ref "C20") (pin "1") (pinfunction "1_1") (pintype "passive"))
      (node (ref "R23") (pin "2") (pinfunction "2_2") (pintype "passive"))
      (node (ref "R24") (pin "2") (pinfunction "2_2") (pintype "passive"))
      (node (ref "R30") (pin "1") (pinfunction "1_1") (pintype "passive"))
      (node (ref "R31") (pin "1") (pinfunction "1_1") (pintype "passive"))
      (node (ref "U3") (pin "1") (pinfunction "REF_1") (pintype "passive"))
    )
    (net (code "41") (name "Net-(U5-OUT_SINK)") (class "Default")
      (node (ref "R32") (pin "2") (pinfunction "2_2") (pintype "passive"))
      (node (ref "U5") (pin "7") (pinfunction "OUT_SINK_7") (pintype "passive"))
    )
    (net (code "42") (name "Net-(U5-OUT_SRC)") (class "Default")
      (node (ref "R33") (pin "2") (pinfunction "2_2") (pintype "passive"))
      (node (ref "U5") (pin "6") (pinfunction "OUT_SRC_6") (pintype "passive"))
    )
    (net (code "43") (name "PGND") (class "Default")
      (node (ref "C10") (pin "2") (pinfunction "2_2") (pintype "passive"))
      (node (ref "C13") (pin "2") (pinfunction "2_2") (pintype "passive"))
      (node (ref "C14") (pin "1") (pinfunction "1_1") (pintype "passive"))
      (node (ref "C16") (pin "1") (pinfunction "1_1") (pintype "passive"))
      (node (ref "C17") (pin "1") (pinfunction "1_1") (pintype "passive"))
      (node (ref "C18") (pin "1") (pinfunction "1_1") (pintype "passive"))
      (node (ref "C2") (pin "2") (pinfunction "2_2") (pintype "passive"))
      (node (ref "C21") (pin "2") (pinfunction "2_2") (pintype "passive"))
      (node (ref "C22") (pin "1") (pinfunction "1_1") (pintype "passive"))
      (node (ref "C25") (pin "1") (pinfunction "1_1") (pintype "passive"))
      (node (ref "C26") (pin "2") (pinfunction "2_2") (pintype "passive"))
      (node (ref "C27") (pin "1") (pinfunction "1_1") (pintype "passive"))
      (node (ref "C9") (pin "1") (pinfunction "1_1") (pintype "passive"))
      (node (ref "D1") (pin "3") (pinfunction "-_3") (pintype "passive"))
      (node (ref "D4") (pin "1") (pinfunction "A_1") (pintype "passive"))
      (node (ref "D8") (pin "2") (pinfunction "K_2") (pintype "passive"))
      (node (ref "P1") (pin "2") (pinfunction "2_2") (pintype "power_in"))
      (node (ref "P4") (pin "2") (pinfunction "2_2") (pintype "power_in"))
      (node (ref "P5") (pin "2") (pinfunction "2_2") (pintype "power_in"))
      (node (ref "R2") (pin "2") (pinfunction "2_2") (pintype "passive"))
      (node (ref "R29") (pin "2") (pinfunction "2_2") (pintype "passive"))
      (node (ref "T1") (pin "4") (pinfunction "4_4") (pintype "passive"))
      (node (ref "T2") (pin "1") (pinfunction "1_1") (pintype "passive"))
      (node (ref "U1") (pin "5") (pinfunction "GND_5") (pintype "passive"))
      (node (ref "U4") (pin "2") (pinfunction "GND_2") (pintype "power_in"))
      (node (ref "U5") (pin "3") (pinfunction "IN-_3") (pintype "passive"))
      (node (ref "U5") (pin "4") (pinfunction "GNDI_4") (pintype "passive"))
      (node (ref "U5") (pin "8") (pinfunction "GNDO_8") (pintype "passive"))
    )
    (net (code "44") (name "PULSE_TR") (class "Default")
      (node (ref "C24") (pin "1") (pinfunction "1_1") (pintype "passive"))
      (node (ref "T2") (pin "8") (pinfunction "8_8") (pintype "passive"))
    )
    (net (code "45") (name "PWM") (class "Default")
      (node (ref "P4") (pin "1") (pinfunction "1_1") (pintype "power_in"))
      (node (ref "R18") (pin "2") (pinfunction "2_2") (pintype "passive"))
      (node (ref "U5") (pin "2") (pinfunction "IN+_2") (pintype "passive"))
    )
    (net (code "46") (name "P_GND") (class "Default")
      (node (ref "R11") (pin "1") (pinfunction "1_1") (pintype "passive"))
      (node (ref "R12") (pin "1") (pinfunction "1_1") (pintype "passive"))
      (node (ref "R13") (pin "1") (pinfunction "1_1") (pintype "passive"))
      (node (ref "R14") (pin "1") (pinfunction "1_1") (pintype "passive"))
    )
    (net (code "47") (name "SRC_T") (class "Default")
      (node (ref "D10") (pin "1") (pinfunction "A_1") (pintype "passive"))
      (node (ref "D11") (pin "1") (pinfunction "A_1") (pintype "passive"))
      (node (ref "D4") (pin "2") (pinfunction "K_2") (pintype "passive"))
      (node (ref "Q1") (pin "3") (pinfunction "S_3") (pintype "passive"))
      (node (ref "Q4") (pin "3") (pinfunction "C_3") (pintype "passive"))
      (node (ref "R38") (pin "2") (pinfunction "2_2") (pintype "passive"))
      (node (ref "T1") (pin "1") (pinfunction "1_1") (pintype "passive"))
      (node (ref "T2") (pin "4") (pinfunction "4_4") (pintype "passive"))
    )
    (net (code "48") (name "VCC") (class "Default")
      (node (ref "C10") (pin "1") (pinfunction "1_1") (pintype "passive"))
      (node (ref "C13") (pin "1") (pinfunction "1_1") (pintype "passive"))
      (node (ref "C14") (pin "2") (pinfunction "2_2") (pintype "passive"))
      (node (ref "C26") (pin "1") (pinfunction "1_1") (pintype "passive"))
      (node (ref "C27") (pin "2") (pinfunction "2_2") (pintype "passive"))
      (node (ref "C9") (pin "2") (pinfunction "2_2") (pintype "passive"))
      (node (ref "P5") (pin "1") (pinfunction "1_1") (pintype "power_in"))
      (node (ref "R19") (pin "2") (pinfunction "2_2") (pintype "passive"))
      (node (ref "R34") (pin "1") (pinfunction "1_1") (pintype "passive"))
      (node (ref "R9") (pin "2") (pinfunction "2_2") (pintype "passive"))
      (node (ref "U1") (pin "7") (pinfunction "VCC_7") (pintype "passive"))
      (node (ref "U4") (pin "1") (pinfunction "VIN_1") (pintype "power_in"))
    )
    (net (code "49") (name "VCC_LR") (class "Default")
      (node (ref "C25") (pin "2") (pinfunction "2_2") (pintype "passive"))
      (node (ref "U4") (pin "3") (pinfunction "VOUT_3") (pintype "power_in"))
      (node (ref "U5") (pin "1") (pinfunction "VDDI_1") (pintype "passive"))
      (node (ref "U5") (pin "5") (pinfunction "VDDO_5") (pintype "passive"))
    )
    (net (code "50") (name "VDCLINK") (class "Default")
      (node (ref "C2") (pin "1") (pinfunction "1_1") (pintype "passive"))
      (node (ref "D2") (pin "2") (pinfunction "K_2") (pintype "passive"))
      (node (ref "P1") (pin "1") (pinfunction "1_1") (pintype "power_in"))
      (node (ref "Q1") (pin "2") (pinfunction "D_2") (pintype "passive"))
      (node (ref "R15") (pin "1") (pinfunction "1_1") (pintype "passive"))
      (node (ref "R2") (pin "1") (pinfunction "1_1") (pintype "passive"))
      (node (ref "RT1") (pin "2") (pinfunction "2_2") (pintype "passive"))
    )
    (net (code "51") (name "VFB") (class "Default")
      (node (ref "C15") (pin "1") (pinfunction "1_1") (pintype "passive"))
      (node (ref "R16") (pin "1") (pinfunction "1_1") (pintype "passive"))
      (node (ref "R26") (pin "1") (pinfunction "1_1") (pintype "passive"))
      (node (ref "U1") (pin "2") (pinfunction "VFB_2") (pintype "passive"))
    )
    (net (code "52") (name "VREF") (class "Default")
      (node (ref "C17") (pin "2") (pinfunction "2_2") (pintype "passive"))
      (node (ref "R20") (pin "2") (pinfunction "2_2") (pintype "passive"))
      (node (ref "U1") (pin "8") (pinfunction "VREF_8") (pintype "passive"))
      (node (ref "U2") (pin "4") (pinfunction "C_4") (pintype "passive"))
    )
    (net (code "53") (name "Vout") (class "Default")
      (node (ref "C1") (pin "1") (pinfunction "1_1") (pintype "passive"))
      (node (ref "C3") (pin "1") (pinfunction "1_1") (pintype "passive"))
      (node (ref "C4") (pin "1") (pinfunction "1_1") (pintype "passive"))
      (node (ref "C5") (pin "1") (pinfunction "1_1") (pintype "passive"))
      (node (ref "C6") (pin "2") (pinfunction "2_2") (pintype "passive"))
      (node (ref "C7") (pin "2") (pinfunction "2_2") (pintype "passive"))
      (node (ref "C8") (pin "2") (pinfunction "2_2") (pintype "passive"))
      (node (ref "D3") (pin "2") (pinfunction "K_2") (pintype "passive"))
      (node (ref "P2") (pin "2") (pinfunction "2_2") (pintype "power_in"))
      (node (ref "Q3") (pin "3") (pinfunction "C_3") (pintype "passive"))
      (node (ref "R10") (pin "1") (pinfunction "1_1") (pintype "passive"))
      (node (ref "R23") (pin "1") (pinfunction "1_1") (pintype "passive"))
      (node (ref "R24") (pin "1") (pinfunction "1_1") (pintype "passive"))
      (node (ref "R27") (pin "1") (pinfunction "1_1") (pintype "passive"))
      (node (ref "R4") (pin "1") (pinfunction "1_1") (pintype "passive"))
      (node (ref "R5") (pin "1") (pinfunction "1_1") (pintype "passive"))
      (node (ref "R6") (pin "1") (pinfunction "1_1") (pintype "passive"))
    )
    (net (code "54") (name "unconnected-(R30-Pad3)") (class "Default")
      (node (ref "R30") (pin "3") (pinfunction "3_3") (pintype "passive+no_connect"))
    )
  )
)
